# Supply_Sampler.net
KiCad netlist of a schematic drawn in Altium Designer
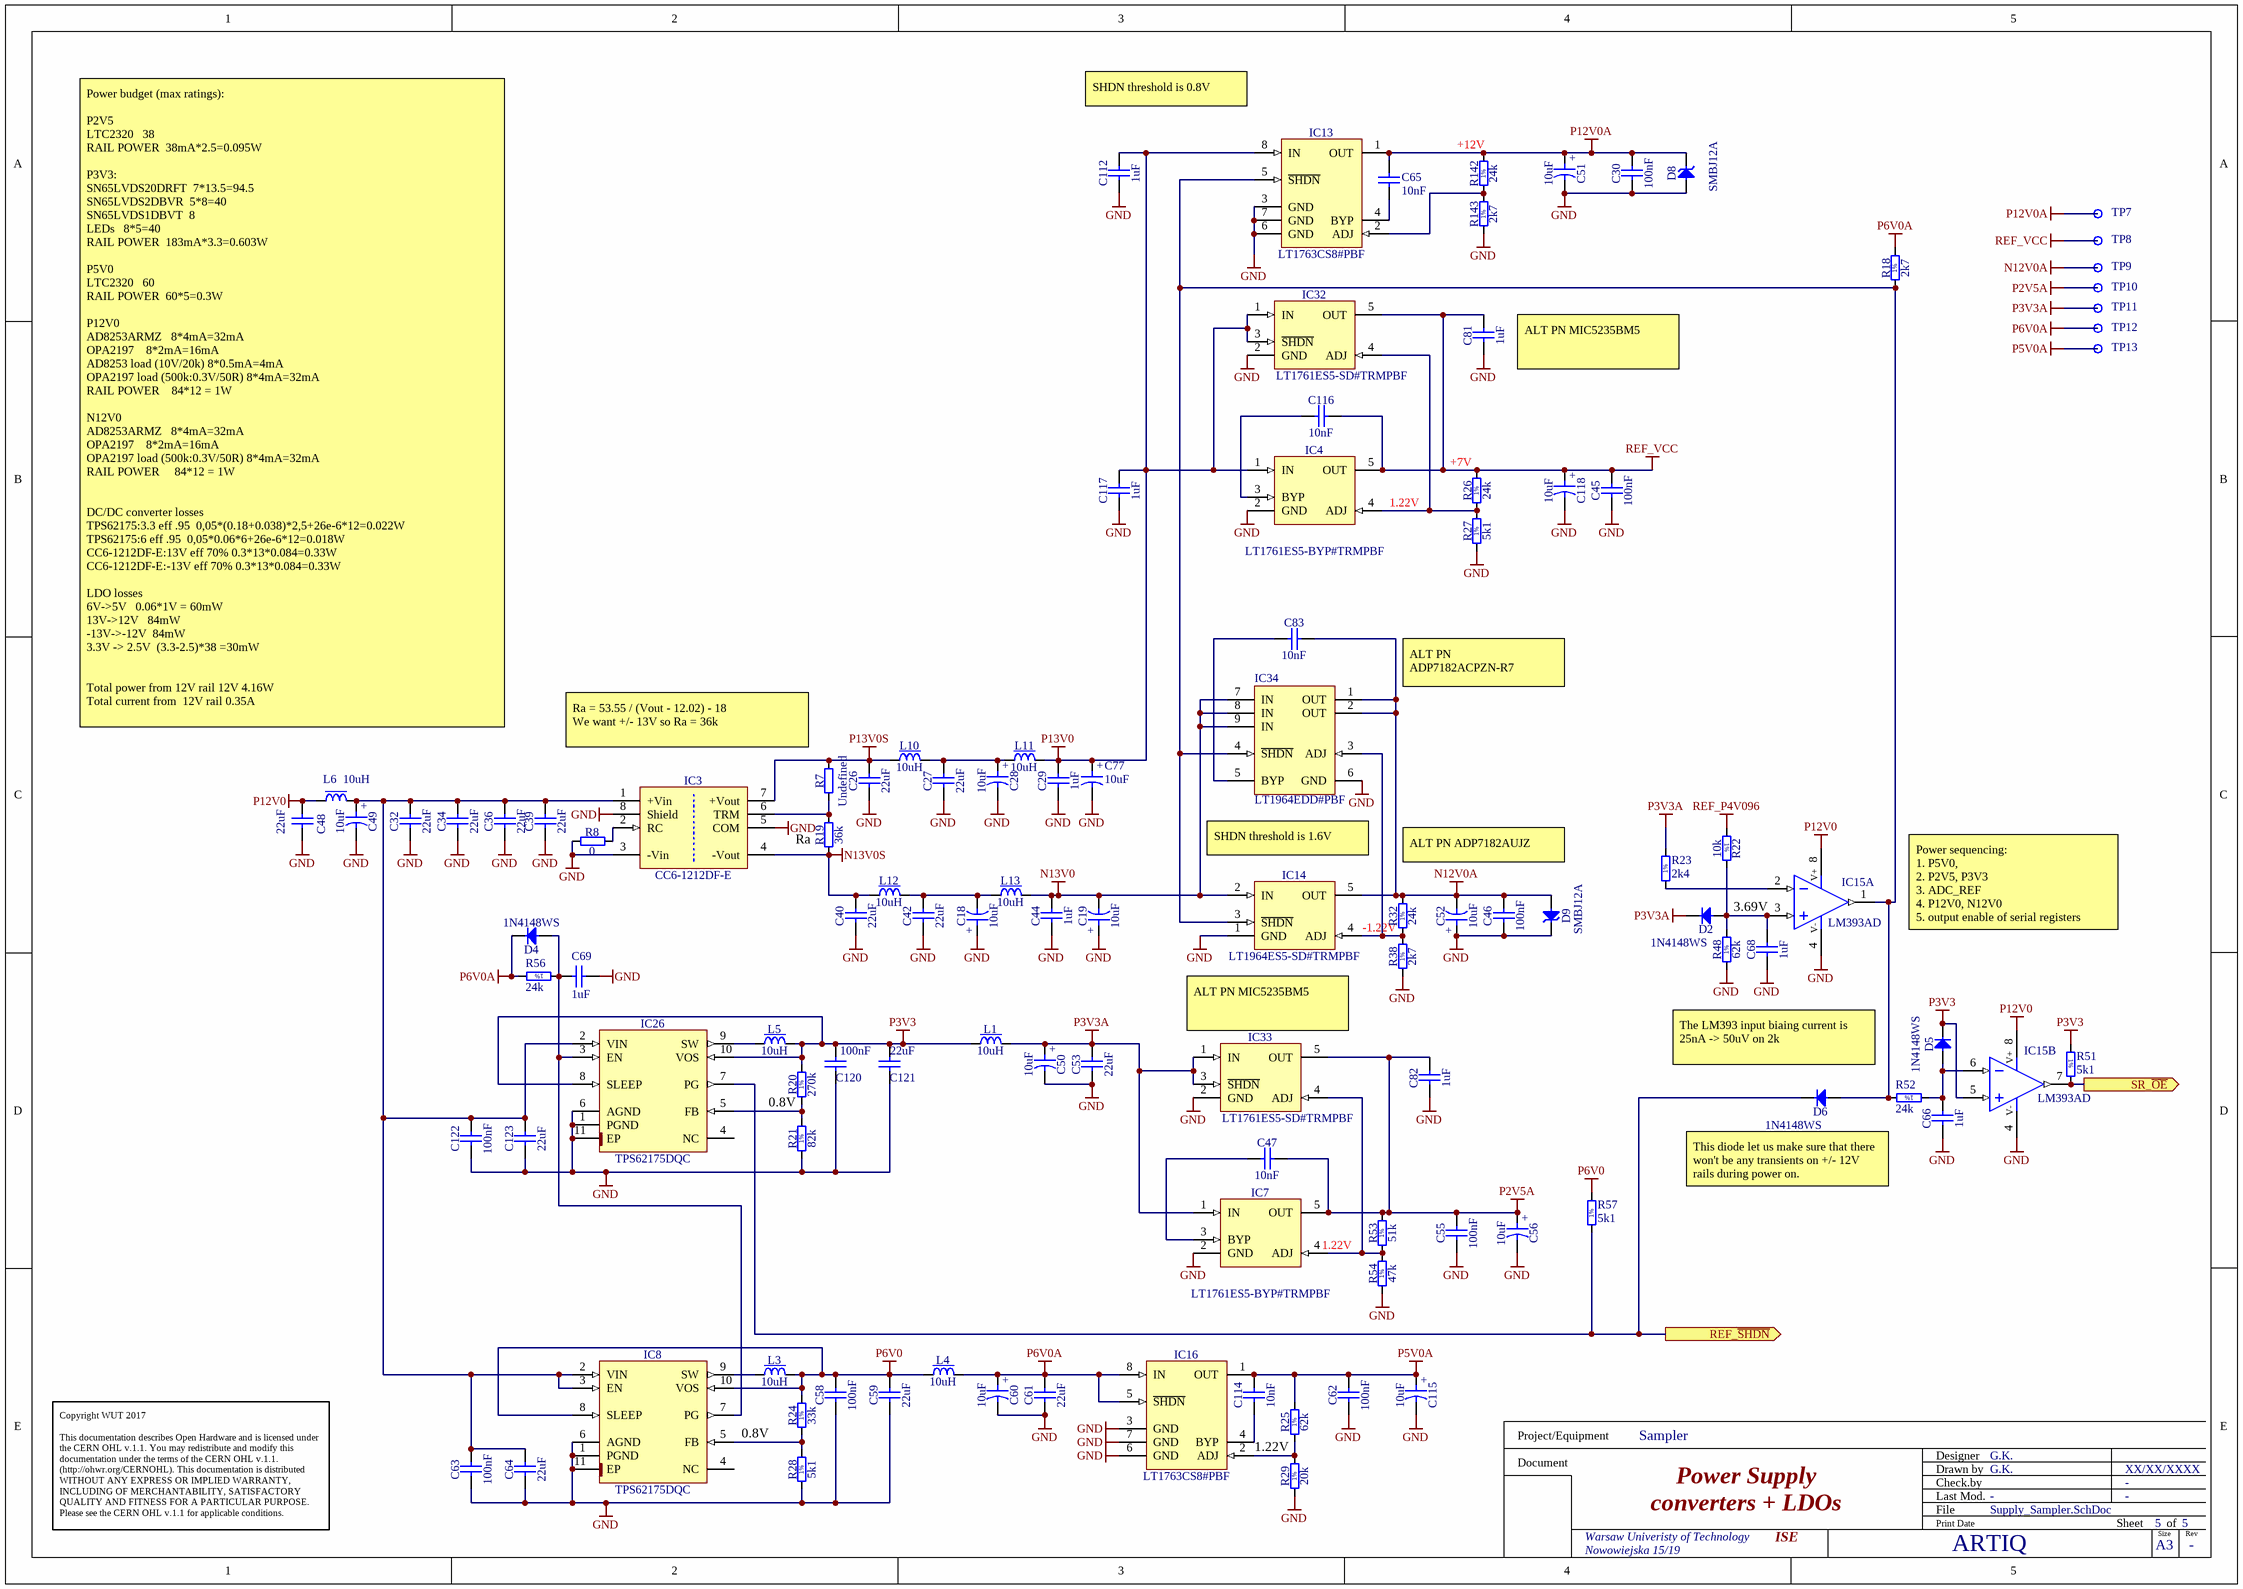
[diagram p0: Supply_Sampler.SchDoc]

(export (version "E")
  (design (tool "Eeschema 10.0.6"))
  (components
    (comp (ref "C18")
      (value "10uF")
      (footprint "CAPMP3216X180N")
      (description "Polarised capacitor")
      (fields (field (name "PART NUMBER") "CTE3216-18_10UF_16V_20%_AVX_TCJ") (field (name "VOLTAGE") "16V"))
      (libsource (lib "Capacitors") (part "Capacitor - polarized"))
    )
    (comp (ref "C19")
      (value "10uF")
      (footprint "CAPMP3216X180N")
      (description "Polarised capacitor")
      (fields (field (name "PART NUMBER") "CTE3216-18_10UF_16V_20%_AVX_TCJ") (field (name "VOLTAGE") "16V"))
      (libsource (lib "Capacitors") (part "Capacitor - polarized"))
    )
    (comp (ref "C26")
      (value "22uF")
      (footprint "CAPC2012X135N")
      (description "Non-polarised capacitor")
      (fields (field (name "PART NUMBER") "CC0805_22UF_16V_10%_X5R") (field (name "VOLTAGE") "16V"))
      (libsource (lib "Capacitors") (part "Capacitor - non polarized"))
    )
    (comp (ref "C27")
      (value "22uF")
      (footprint "CAPC2012X135N")
      (description "Non-polarised capacitor")
      (fields (field (name "PART NUMBER") "CC0805_22UF_16V_10%_X5R") (field (name "VOLTAGE") "16V"))
      (libsource (lib "Capacitors") (part "Capacitor - non polarized"))
    )
    (comp (ref "C28")
      (value "10uF")
      (footprint "CAPMP3216X180N")
      (description "Polarised capacitor")
      (fields (field (name "PART NUMBER") "CTE3216-18_10UF_16V_20%_AVX_TCJ") (field (name "VOLTAGE") "16V"))
      (libsource (lib "Capacitors") (part "Capacitor - polarized"))
    )
    (comp (ref "C29")
      (value "1uF")
      (footprint "CAPC1608X87N")
      (description "Non-polarised capacitor")
      (fields (field (name "PART NUMBER") "CC0603_1UF_25V_10%_X7R") (field (name "VOLTAGE") "25V"))
      (libsource (lib "Capacitors") (part "Capacitor - non polarized"))
    )
    (comp (ref "C30")
      (value "100nF")
      (footprint "CAPC1005X55N")
      (description "Non-polarised capacitor")
      (fields (field (name "PART NUMBER") "CC0402_100NF_16V_10%_X5R") (field (name "VOLTAGE") "16V"))
      (libsource (lib "Capacitors") (part "Capacitor - non polarized"))
    )
    (comp (ref "C32")
      (value "22uF")
      (footprint "CAPC2012X135N")
      (description "Non-polarised capacitor")
      (fields (field (name "PART NUMBER") "CC0805_22UF_16V_10%_X5R") (field (name "VOLTAGE") "16V"))
      (libsource (lib "Capacitors") (part "Capacitor - non polarized"))
    )
    (comp (ref "C34")
      (value "22uF")
      (footprint "CAPC2012X135N")
      (description "Non-polarised capacitor")
      (fields (field (name "PART NUMBER") "CC0805_22UF_16V_10%_X5R") (field (name "VOLTAGE") "16V"))
      (libsource (lib "Capacitors") (part "Capacitor - non polarized"))
    )
    (comp (ref "C36")
      (value "22uF")
      (footprint "CAPC2012X135N")
      (description "Non-polarised capacitor")
      (fields (field (name "PART NUMBER") "CC0805_22UF_16V_10%_X5R") (field (name "VOLTAGE") "16V"))
      (libsource (lib "Capacitors") (part "Capacitor - non polarized"))
    )
    (comp (ref "C39")
      (value "22uF")
      (footprint "CAPC2012X135N")
      (description "Non-polarised capacitor")
      (fields (field (name "PART NUMBER") "CC0805_22UF_16V_10%_X5R") (field (name "VOLTAGE") "16V"))
      (libsource (lib "Capacitors") (part "Capacitor - non polarized"))
    )
    (comp (ref "C40")
      (value "22uF")
      (footprint "CAPC2012X135N")
      (description "Non-polarised capacitor")
      (fields (field (name "PART NUMBER") "CC0805_22UF_16V_10%_X5R") (field (name "VOLTAGE") "16V"))
      (libsource (lib "Capacitors") (part "Capacitor - non polarized"))
    )
    (comp (ref "C42")
      (value "22uF")
      (footprint "CAPC2012X135N")
      (description "Non-polarised capacitor")
      (fields (field (name "PART NUMBER") "CC0805_22UF_16V_10%_X5R") (field (name "VOLTAGE") "16V"))
      (libsource (lib "Capacitors") (part "Capacitor - non polarized"))
    )
    (comp (ref "C44")
      (value "1uF")
      (footprint "CAPC1608X87N")
      (description "Non-polarised capacitor")
      (fields (field (name "PART NUMBER") "CC0603_1UF_25V_10%_X7R") (field (name "VOLTAGE") "25V"))
      (libsource (lib "Capacitors") (part "Capacitor - non polarized"))
    )
    (comp (ref "C45")
      (value "100nF")
      (footprint "CAPC1005X55N")
      (description "Non-polarised capacitor")
      (fields (field (name "PART NUMBER") "CC0402_100NF_16V_10%_X5R") (field (name "VOLTAGE") "16V"))
      (libsource (lib "Capacitors") (part "Capacitor - non polarized"))
    )
    (comp (ref "C46")
      (value "100nF")
      (footprint "CAPC1005X55N")
      (description "Non-polarised capacitor")
      (fields (field (name "PART NUMBER") "CC0402_100NF_16V_10%_X5R") (field (name "VOLTAGE") "16V"))
      (libsource (lib "Capacitors") (part "Capacitor - non polarized"))
    )
    (comp (ref "C47")
      (value "10nF")
      (footprint "CAPC1608X87N")
      (description "Non-polarised capacitor")
      (fields (field (name "PART NUMBER") "CC0603_10NF_50V_10%_X7R") (field (name "VOLTAGE") "50V"))
      (libsource (lib "Capacitors") (part "Capacitor - non polarized"))
    )
    (comp (ref "C48")
      (value "22uF")
      (footprint "CAPC2012X135N")
      (description "Non-polarised capacitor")
      (fields (field (name "PART NUMBER") "CC0805_22UF_16V_10%_X5R") (field (name "VOLTAGE") "16V"))
      (libsource (lib "Capacitors") (part "Capacitor - non polarized"))
    )
    (comp (ref "C49")
      (value "10uF")
      (footprint "CAPMP3216X180N")
      (description "Polarised capacitor")
      (fields (field (name "PART NUMBER") "CTE3216-18_10UF_16V_20%_AVX_TCJ") (field (name "VOLTAGE") "16V"))
      (libsource (lib "Capacitors") (part "Capacitor - polarized"))
    )
    (comp (ref "C50")
      (value "10uF")
      (footprint "CAPMP3216X180N")
      (description "Polarised capacitor")
      (fields (field (name "PART NUMBER") "CTE3216-18_10UF_16V_20%_AVX_TCJ") (field (name "VOLTAGE") "16V"))
      (libsource (lib "Capacitors") (part "Capacitor - polarized"))
    )
    (comp (ref "C51")
      (value "10uF")
      (footprint "CAPMP3216X180N")
      (description "Polarised capacitor")
      (fields (field (name "PART NUMBER") "CTE3216-18_10UF_16V_20%_AVX_TCJ") (field (name "VOLTAGE") "16V"))
      (libsource (lib "Capacitors") (part "Capacitor - polarized"))
    )
    (comp (ref "C52")
      (value "10uF")
      (footprint "CAPMP3216X180N")
      (description "Polarised capacitor")
      (fields (field (name "PART NUMBER") "CTE3216-18_10UF_16V_20%_AVX_TCJ") (field (name "VOLTAGE") "16V"))
      (libsource (lib "Capacitors") (part "Capacitor - polarized"))
    )
    (comp (ref "C53")
      (value "22uF")
      (footprint "CAPC2012X135N")
      (description "Non-polarised capacitor")
      (fields (field (name "PART NUMBER") "CC0805_22UF_16V_10%_X5R") (field (name "VOLTAGE") "16V"))
      (libsource (lib "Capacitors") (part "Capacitor - non polarized"))
    )
    (comp (ref "C55")
      (value "100nF")
      (footprint "CAPC1005X55N")
      (description "Non-polarised capacitor")
      (fields (field (name "PART NUMBER") "CC0402_100NF_16V_10%_X5R") (field (name "VOLTAGE") "16V"))
      (libsource (lib "Capacitors") (part "Capacitor - non polarized"))
    )
    (comp (ref "C56")
      (value "10uF")
      (footprint "CAPMP3216X180N")
      (description "Polarised capacitor")
      (fields (field (name "PART NUMBER") "CTE3216-18_10UF_16V_20%_AVX_TCJ") (field (name "VOLTAGE") "16V"))
      (libsource (lib "Capacitors") (part "Capacitor - polarized"))
    )
    (comp (ref "C58")
      (value "100nF")
      (footprint "CAPC1005X55N")
      (description "Non-polarised capacitor")
      (fields (field (name "PART NUMBER") "CC0402_100NF_16V_10%_X5R") (field (name "VOLTAGE") "16V"))
      (libsource (lib "Capacitors") (part "Capacitor - non polarized"))
    )
    (comp (ref "C59")
      (value "22uF")
      (footprint "CAPC2012X135N")
      (description "Non-polarised capacitor")
      (fields (field (name "PART NUMBER") "CC0805_22UF_16V_10%_X5R") (field (name "VOLTAGE") "16V"))
      (libsource (lib "Capacitors") (part "Capacitor - non polarized"))
    )
    (comp (ref "C60")
      (value "10uF")
      (footprint "CAPMP3216X180N")
      (description "Polarised capacitor")
      (fields (field (name "PART NUMBER") "CTE3216-18_10UF_16V_20%_AVX_TCJ") (field (name "VOLTAGE") "16V"))
      (libsource (lib "Capacitors") (part "Capacitor - polarized"))
    )
    (comp (ref "C61")
      (value "22uF")
      (footprint "CAPC2012X135N")
      (description "Non-polarised capacitor")
      (fields (field (name "PART NUMBER") "CC0805_22UF_16V_10%_X5R") (field (name "VOLTAGE") "16V"))
      (libsource (lib "Capacitors") (part "Capacitor - non polarized"))
    )
    (comp (ref "C62")
      (value "100nF")
      (footprint "CAPC1005X55N")
      (description "Non-polarised capacitor")
      (fields (field (name "PART NUMBER") "CC0402_100NF_16V_10%_X5R") (field (name "VOLTAGE") "16V"))
      (libsource (lib "Capacitors") (part "Capacitor - non polarized"))
    )
    (comp (ref "C63")
      (value "100nF")
      (footprint "CAPC1005X55N")
      (description "Non-polarised capacitor")
      (fields (field (name "PART NUMBER") "CC0402_100NF_16V_10%_X5R") (field (name "VOLTAGE") "16V"))
      (libsource (lib "Capacitors") (part "Capacitor - non polarized"))
    )
    (comp (ref "C64")
      (value "22uF")
      (footprint "CAPC2012X135N")
      (description "Non-polarised capacitor")
      (fields (field (name "PART NUMBER") "CC0805_22UF_16V_10%_X5R") (field (name "VOLTAGE") "16V"))
      (libsource (lib "Capacitors") (part "Capacitor - non polarized"))
    )
    (comp (ref "C65")
      (value "10nF")
      (footprint "CAPC1608X87N")
      (description "Non-polarised capacitor")
      (fields (field (name "PART NUMBER") "CC0603_10NF_50V_10%_X7R") (field (name "VOLTAGE") "50V"))
      (libsource (lib "Capacitors") (part "Capacitor - non polarized"))
    )
    (comp (ref "C66")
      (value "1uF")
      (footprint "CAPC1608X87N")
      (description "Non-polarised capacitor")
      (fields (field (name "PART NUMBER") "CC0603_1UF_25V_10%_X7R") (field (name "VOLTAGE") "25V"))
      (libsource (lib "Capacitors") (part "Capacitor - non polarized"))
    )
    (comp (ref "C68")
      (value "1uF")
      (footprint "CAPC1608X87N")
      (description "Non-polarised capacitor")
      (fields (field (name "PART NUMBER") "CC0603_1UF_25V_10%_X7R") (field (name "VOLTAGE") "25V"))
      (libsource (lib "Capacitors") (part "Capacitor - non polarized"))
    )
    (comp (ref "C69")
      (value "1uF")
      (footprint "CAPC1608X87N")
      (description "Non-polarised capacitor")
      (fields (field (name "PART NUMBER") "CC0603_1UF_25V_10%_X7R") (field (name "VOLTAGE") "25V"))
      (libsource (lib "Capacitors") (part "Capacitor - non polarized"))
    )
    (comp (ref "C77")
      (value "10uF")
      (footprint "CAPMP3216X180N")
      (description "Polarised capacitor")
      (fields (field (name "PART NUMBER") "CTE3216-18_10UF_16V_20%_AVX_TCJ") (field (name "VOLTAGE") "16V"))
      (libsource (lib "Capacitors") (part "Capacitor - polarized"))
    )
    (comp (ref "C81")
      (value "1uF")
      (footprint "CAPC1608X87N")
      (description "Non-polarised capacitor")
      (fields (field (name "PART NUMBER") "CC0603_1UF_25V_10%_X7R") (field (name "VOLTAGE") "25V"))
      (libsource (lib "Capacitors") (part "Capacitor - non polarized"))
    )
    (comp (ref "C82")
      (value "1uF")
      (footprint "CAPC1608X87N")
      (description "Non-polarised capacitor")
      (fields (field (name "PART NUMBER") "CC0603_1UF_25V_10%_X7R") (field (name "VOLTAGE") "25V"))
      (libsource (lib "Capacitors") (part "Capacitor - non polarized"))
    )
    (comp (ref "C83")
      (value "10nF")
      (footprint "CAPC1608X87N")
      (description "Non-polarised capacitor")
      (fields (field (name "PART NUMBER") "CC0603_10NF_50V_10%_X7R") (field (name "VOLTAGE") "50V"))
      (libsource (lib "Capacitors") (part "Capacitor - non polarized"))
    )
    (comp (ref "C112")
      (value "1uF")
      (footprint "CAPC1608X87N")
      (description "Non-polarised capacitor")
      (fields (field (name "PART NUMBER") "CC0603_1UF_25V_10%_X7R") (field (name "VOLTAGE") "25V"))
      (libsource (lib "Capacitors") (part "Capacitor - non polarized"))
    )
    (comp (ref "C114")
      (value "10nF")
      (footprint "CAPC1608X87N")
      (description "Non-polarised capacitor")
      (fields (field (name "PART NUMBER") "CC0603_10NF_50V_10%_X7R") (field (name "VOLTAGE") "50V"))
      (libsource (lib "Capacitors") (part "Capacitor - non polarized"))
    )
    (comp (ref "C115")
      (value "10uF")
      (footprint "CAPMP3216X180N")
      (description "Polarised capacitor")
      (fields (field (name "PART NUMBER") "CTE3216-18_10UF_16V_20%_AVX_TCJ") (field (name "VOLTAGE") "16V"))
      (libsource (lib "Capacitors") (part "Capacitor - polarized"))
    )
    (comp (ref "C116")
      (value "10nF")
      (footprint "CAPC1608X87N")
      (description "Non-polarised capacitor")
      (fields (field (name "PART NUMBER") "CC0603_10NF_50V_10%_X7R") (field (name "VOLTAGE") "50V"))
      (libsource (lib "Capacitors") (part "Capacitor - non polarized"))
    )
    (comp (ref "C117")
      (value "1uF")
      (footprint "CAPC1608X87N")
      (description "Non-polarised capacitor")
      (fields (field (name "PART NUMBER") "CC0603_1UF_25V_10%_X7R") (field (name "VOLTAGE") "25V"))
      (libsource (lib "Capacitors") (part "Capacitor - non polarized"))
    )
    (comp (ref "C118")
      (value "10uF")
      (footprint "CAPMP3216X180N")
      (description "Polarised capacitor")
      (fields (field (name "PART NUMBER") "CTE3216-18_10UF_16V_20%_AVX_TCJ") (field (name "VOLTAGE") "16V"))
      (libsource (lib "Capacitors") (part "Capacitor - polarized"))
    )
    (comp (ref "C120")
      (value "100nF")
      (footprint "CAPC1005X55N")
      (description "Non-polarised capacitor")
      (fields (field (name "PART NUMBER") "CC0402_100NF_16V_10%_X5R") (field (name "VOLTAGE") "16V"))
      (libsource (lib "Capacitors") (part "Capacitor - non polarized"))
    )
    (comp (ref "C121")
      (value "22uF")
      (footprint "CAPC2012X135N")
      (description "Non-polarised capacitor")
      (fields (field (name "PART NUMBER") "CC0805_22UF_16V_10%_X5R") (field (name "VOLTAGE") "16V"))
      (libsource (lib "Capacitors") (part "Capacitor - non polarized"))
    )
    (comp (ref "C122")
      (value "100nF")
      (footprint "CAPC1005X55N")
      (description "Non-polarised capacitor")
      (fields (field (name "PART NUMBER") "CC0402_100NF_16V_10%_X5R") (field (name "VOLTAGE") "16V"))
      (libsource (lib "Capacitors") (part "Capacitor - non polarized"))
    )
    (comp (ref "C123")
      (value "22uF")
      (footprint "CAPC2012X135N")
      (description "Non-polarised capacitor")
      (fields (field (name "PART NUMBER") "CC0805_22UF_16V_10%_X5R") (field (name "VOLTAGE") "16V"))
      (libsource (lib "Capacitors") (part "Capacitor - non polarized"))
    )
    (comp (ref "D2")
      (value "1N4148WS")
      (footprint "SODFL2512X100N")
      (description "Diode")
      (fields (field (name "VOLTAGE") "75V") (field (name "POWER") "150mA"))
      (libsource (lib "ICs And Semiconductors") (part "Diode"))
    )
    (comp (ref "D4")
      (value "1N4148WS")
      (footprint "SODFL2512X100N")
      (description "Diode")
      (fields (field (name "VOLTAGE") "75V") (field (name "POWER") "150mA"))
      (libsource (lib "ICs And Semiconductors") (part "Diode"))
    )
    (comp (ref "D5")
      (value "1N4148WS")
      (footprint "SODFL2512X100N")
      (description "Diode")
      (fields (field (name "VOLTAGE") "75V") (field (name "POWER") "150mA"))
      (libsource (lib "ICs And Semiconductors") (part "Diode"))
    )
    (comp (ref "D6")
      (value "1N4148WS")
      (footprint "SODFL2512X100N")
      (description "Diode")
      (fields (field (name "VOLTAGE") "75V") (field (name "POWER") "150mA"))
      (libsource (lib "ICs And Semiconductors") (part "Diode"))
    )
    (comp (ref "D8")
      (value "SMBJ12A")
      (footprint "DIOM5336X265N")
      (description "Zener Diode")
      (fields (field (name "VOLTAGE") "12V") (field (name "POWER") "600W"))
      (libsource (lib "ICs And Semiconductors") (part "Diode Zener"))
    )
    (comp (ref "D9")
      (value "SMBJ12A")
      (footprint "DIOM5336X265N")
      (description "Zener Diode")
      (fields (field (name "VOLTAGE") "12V") (field (name "POWER") "600W"))
      (libsource (lib "ICs And Semiconductors") (part "Diode Zener"))
    )
    (comp (ref "IC3")
      (value "CC6-1212DF-E")
      (footprint "CC6-1212DF-E")
      (description "CONV DC/DC 6W DUAL 12V +-12V PCB")
      (fields (field (name "MANUFACTURER") "TDK-Lambda Americas Inc."))
      (libsource (lib "Regulators_SMPS") (part "DC/DC_CC6-1212DF-E"))
    )
    (comp (ref "IC4")
      (value "LT1761ES5-BYP#TRMPBF")
      (footprint "SOT95P280X100-5N")
      (description "100mA, Low Noise, LDO Micropower Adjustable Regulator in SOT-23")
      (fields (field (name "MANUFACTURER") "LINEAR TECHNOLOGY"))
      (libsource (lib "ICs And Semiconductors") (part "LT1761-BYP"))
    )
    (comp (ref "IC7")
      (value "LT1761ES5-BYP#TRMPBF")
      (footprint "SOT95P280X100-5N")
      (description "100mA, Low Noise, LDO Micropower Adjustable Regulator in SOT-23")
      (fields (field (name "MANUFACTURER") "LINEAR TECHNOLOGY"))
      (libsource (lib "ICs And Semiconductors") (part "LT1761-BYP"))
    )
    (comp (ref "IC8")
      (value "TPS62175DQC")
      (footprint "SON50P200X300X80-11N-R94X250")
      (description "4.75-28VDC to 1-6VDC, 500mA Step-Down Converter With Sleep Mode")
      (fields (field (name "MANUFACTURER") "TEXAS INSTRUMENTS"))
      (libsource (lib "ICs And Semiconductors") (part "TPS62175"))
    )
    (comp (ref "IC13")
      (value "LT1763CS8#PBF")
      (footprint "SOIC127P600X175-8N")
      (description "1.22V to 20V 500mA, Low Noise, LDO Adjustable Micropower Regulator")
      (fields (field (name "MANUFACTURER") "LINEAR TECHNOLOGY"))
      (libsource (lib "ICs And Semiconductors") (part "LT1763xS8"))
    )
    (comp (ref "IC14")
      (value "LT1964ES5-SD#TRMPBF")
      (footprint "SOT95P280X100-5N")
      (description "200mA, Low Noise, Low Dropout Negative Micropower Regulator")
      (fields (field (name "MANUFACTURER") "LINEAR TECHNOLOGY"))
      (libsource (lib "ICs And Semiconductors") (part "LT1964-SD"))
    )
    (comp (ref "IC15")
      (value "LM393AD")
      (footprint "SOIC127P600X175-8N")
      (description "Dual Operational Amplifier")
      (fields (field (name "MANUFACTURER") "TEXAS INSTRUMENTS"))
      (libsource (lib "ICs And Semiconductors") (part "Operational Amplifier x2 Type1"))
    )
    (comp (ref "IC16")
      (value "LT1763CS8#PBF")
      (footprint "SOIC127P600X175-8N")
      (description "1.22V to 20V 500mA, Low Noise, LDO Adjustable Micropower Regulator")
      (fields (field (name "MANUFACTURER") "LINEAR TECHNOLOGY"))
      (libsource (lib "ICs And Semiconductors") (part "LT1763xS8"))
    )
    (comp (ref "IC26")
      (value "TPS62175DQC")
      (footprint "SON50P200X300X80-11N-R94X250")
      (description "4.75-28VDC to 1-6VDC, 500mA Step-Down Converter With Sleep Mode")
      (fields (field (name "MANUFACTURER") "TEXAS INSTRUMENTS"))
      (libsource (lib "ICs And Semiconductors") (part "TPS62175"))
    )
    (comp (ref "IC32")
      (value "LT1761ES5-SD#TRMPBF")
      (footprint "SOT95P280X100-5N")
      (description "100mA, Low Noise, LDO Micropower Adjustable Regulator in SOT-23")
      (fields (field (name "MANUFACTURER") "LINEAR TECHNOLOGY"))
      (libsource (lib "ICs And Semiconductors") (part "LT1761-SD"))
    )
    (comp (ref "IC33")
      (value "LT1761ES5-SD#TRMPBF")
      (footprint "SOT95P280X100-5N")
      (description "100mA, Low Noise, LDO Micropower Adjustable Regulator in SOT-23")
      (fields (field (name "MANUFACTURER") "LINEAR TECHNOLOGY"))
      (libsource (lib "ICs And Semiconductors") (part "LT1761-SD"))
    )
    (comp (ref "IC34")
      (value "LT1964EDD#PBF")
      (footprint "LT-DD-8_V")
      (fields (field (name "MANUFACTURER") "Linear Technology"))
      (libsource (lib "Altium Content Vault") (part "LT-LT1964-DD-8"))
    )
    (comp (ref "L1")
      (value "10uH")
      (footprint "IND_MURATA-PS_8400")
      (description "Inductor With Core")
      (fields (field (name "PART NUMBER") "IND_10UH_10%_MURATA-PS_8400") (field (name "POWER") "950mA"))
      (libsource (lib "Inductors & Transformers") (part "Inductor With Magnetic core"))
    )
    (comp (ref "L3")
      (value "10uH")
      (footprint "IND_MURATA-PS_8400")
      (description "Inductor With Core")
      (fields (field (name "PART NUMBER") "IND_10UH_10%_MURATA-PS_8400") (field (name "POWER") "950mA"))
      (libsource (lib "Inductors & Transformers") (part "Inductor With Magnetic core"))
    )
    (comp (ref "L4")
      (value "10uH")
      (footprint "IND_MURATA-PS_8400")
      (description "Inductor With Core")
      (fields (field (name "PART NUMBER") "IND_10UH_10%_MURATA-PS_8400") (field (name "POWER") "950mA"))
      (libsource (lib "Inductors & Transformers") (part "Inductor With Magnetic core"))
    )
    (comp (ref "L5")
      (value "10uH")
      (footprint "IND_MURATA-PS_8400")
      (description "Inductor With Core")
      (fields (field (name "PART NUMBER") "IND_10UH_10%_MURATA-PS_8400") (field (name "POWER") "950mA"))
      (libsource (lib "Inductors & Transformers") (part "Inductor With Magnetic core"))
    )
    (comp (ref "L6")
      (value "10uH")
      (footprint "IND_MURATA-PS_8400")
      (description "Inductor With Core")
      (fields (field (name "PART NUMBER") "IND_10UH_10%_MURATA-PS_8400") (field (name "POWER") "950mA"))
      (libsource (lib "Inductors & Transformers") (part "Inductor With Magnetic core"))
    )
    (comp (ref "L10")
      (value "10uH")
      (footprint "IND_MURATA-PS_8400")
      (description "Inductor With Core")
      (fields (field (name "PART NUMBER") "IND_10UH_10%_MURATA-PS_8400") (field (name "POWER") "950mA"))
      (libsource (lib "Inductors & Transformers") (part "Inductor With Magnetic core"))
    )
    (comp (ref "L11")
      (value "10uH")
      (footprint "IND_MURATA-PS_8400")
      (description "Inductor With Core")
      (fields (field (name "PART NUMBER") "IND_10UH_10%_MURATA-PS_8400") (field (name "POWER") "950mA"))
      (libsource (lib "Inductors & Transformers") (part "Inductor With Magnetic core"))
    )
    (comp (ref "L12")
      (value "10uH")
      (footprint "IND_MURATA-PS_8400")
      (description "Inductor With Core")
      (fields (field (name "PART NUMBER") "IND_10UH_10%_MURATA-PS_8400") (field (name "POWER") "950mA"))
      (libsource (lib "Inductors & Transformers") (part "Inductor With Magnetic core"))
    )
    (comp (ref "L13")
      (value "10uH")
      (footprint "IND_MURATA-PS_8400")
      (description "Inductor With Core")
      (fields (field (name "PART NUMBER") "IND_10UH_10%_MURATA-PS_8400") (field (name "POWER") "950mA"))
      (libsource (lib "Inductors & Transformers") (part "Inductor With Magnetic core"))
    )
    (comp (ref "R7")
      (value "Undefined")
      (footprint "RESC1608X55N")
      (description "Resistor")
      (fields (field (name "PART NUMBER") "R0603_NO-VALUE"))
      (libsource (lib "Resistors") (part "Resistor"))
    )
    (comp (ref "R8")
      (value "0")
      (footprint "RESC1005X40N")
      (description "Resistor")
      (fields (field (name "PART NUMBER") "R0402_0R_JUMPER") (field (name "MANUFACTURER") "GENERIC"))
      (libsource (lib "Resistors") (part "Resistor"))
    )
    (comp (ref "R18")
      (value "2k7")
      (footprint "RESC1608X55N")
      (description "Resistor - 1%")
      (fields (field (name "PART NUMBER") "R0603_2K7_1%_0.1W_100PPM") (field (name "POWER") "0.1W"))
      (libsource (lib "Resistors") (part "Resistor - 1%"))
    )
    (comp (ref "R19")
      (value "36k")
      (footprint "RESC1608X55N")
      (description "Resistor - 1%")
      (fields (field (name "PART NUMBER") "R0603_36K_1%_0.1W_100PPM") (field (name "POWER") "0.1W"))
      (libsource (lib "") (part "Resistor - 1%_1"))
    )
    (comp (ref "R20")
      (value "270k")
      (footprint "RESC1608X55N")
      (description "Resistor - 1%")
      (fields (field (name "PART NUMBER") "R0603_270K_1%_0.1W_100PPM") (field (name "POWER") "0.1W"))
      (libsource (lib "Resistors") (part "Resistor - 1%"))
    )
    (comp (ref "R21")
      (value "82k")
      (footprint "RESC1608X55N")
      (description "Resistor - 1%")
      (fields (field (name "PART NUMBER") "R0603_82K_1%_0.1W_100PPM") (field (name "POWER") "0.1W"))
      (libsource (lib "Resistors") (part "Resistor - 1%"))
    )
    (comp (ref "R22")
      (value "10k")
      (footprint "RESC1005X40N")
      (description "Resistor - 1%")
      (fields (field (name "PART NUMBER") "R0402_10K_1%_0.0625W_100PPM") (field (name "POWER") "0.0625W"))
      (libsource (lib "Resistors") (part "Resistor - 1%"))
    )
    (comp (ref "R23")
      (value "2k4")
      (footprint "RESC1005X40N")
      (description "Resistor - 1%")
      (fields (field (name "PART NUMBER") "R0402_2K4_1%_0.0625W_100PPM") (field (name "POWER") "0.0625W"))
      (libsource (lib "Resistors") (part "Resistor - 1%"))
    )
    (comp (ref "R24")
      (value "33k")
      (footprint "RESC1005X40N")
      (description "Resistor - 1%")
      (fields (field (name "PART NUMBER") "R0402_33K_1%_0.0625W_100PPM") (field (name "POWER") "0.0625W"))
      (libsource (lib "Resistors") (part "Resistor - 1%"))
    )
    (comp (ref "R25")
      (value "62k")
      (footprint "RESC1005X40N")
      (description "Resistor - 1%")
      (fields (field (name "PART NUMBER") "R0402_62K_1%_0.0625W_100PPM") (field (name "POWER") "0.0625W"))
      (libsource (lib "Resistors") (part "Resistor - 1%"))
    )
    (comp (ref "R26")
      (value "24k")
      (footprint "RESC1608X55N")
      (description "Resistor - 1%")
      (fields (field (name "PART NUMBER") "R0603_24K_1%_0.1W_100PPM") (field (name "POWER") "0.1W"))
      (libsource (lib "Resistors") (part "Resistor - 1%"))
    )
    (comp (ref "R27")
      (value "5k1")
      (footprint "RESC1005X40N")
      (description "Resistor - 1%")
      (fields (field (name "PART NUMBER") "R0402_5K1_1%_0.0625W_100PPM") (field (name "POWER") "0.0625W"))
      (libsource (lib "Resistors") (part "Resistor - 1%"))
    )
    (comp (ref "R28")
      (value "5k1")
      (footprint "RESC1005X40N")
      (description "Resistor - 1%")
      (fields (field (name "PART NUMBER") "R0402_5K1_1%_0.0625W_100PPM") (field (name "POWER") "0.0625W"))
      (libsource (lib "Resistors") (part "Resistor - 1%"))
    )
    (comp (ref "R29")
      (value "20k")
      (footprint "RESC1005X40N")
      (description "Resistor - 1%")
      (fields (field (name "PART NUMBER") "R0402_20K_1%_0.0625W_100PPM") (field (name "POWER") "0.0625W"))
      (libsource (lib "Resistors") (part "Resistor - 1%"))
    )
    (comp (ref "R32")
      (value "24k")
      (footprint "RESC1608X55N")
      (description "Resistor - 1%")
      (fields (field (name "PART NUMBER") "R0603_24K_1%_0.1W_100PPM") (field (name "POWER") "0.1W"))
      (libsource (lib "Resistors") (part "Resistor - 1%"))
    )
    (comp (ref "R38")
      (value "2k7")
      (footprint "RESC1608X55N")
      (description "Resistor - 1%")
      (fields (field (name "PART NUMBER") "R0603_2K7_1%_0.1W_100PPM") (field (name "POWER") "0.1W"))
      (libsource (lib "Resistors") (part "Resistor - 1%"))
    )
    (comp (ref "R48")
      (value "62k")
      (footprint "RESC1005X40N")
      (description "Resistor - 1%")
      (fields (field (name "PART NUMBER") "R0402_62K_1%_0.0625W_100PPM") (field (name "POWER") "0.0625W"))
      (libsource (lib "Resistors") (part "Resistor - 1%"))
    )
    (comp (ref "R51")
      (value "5k1")
      (footprint "RESC1005X40N")
      (description "Resistor - 1%")
      (fields (field (name "PART NUMBER") "R0402_5K1_1%_0.0625W_100PPM") (field (name "POWER") "0.0625W"))
      (libsource (lib "Resistors") (part "Resistor - 1%"))
    )
    (comp (ref "R52")
      (value "24k")
      (footprint "RESC1608X55N")
      (description "Resistor - 1%")
      (fields (field (name "PART NUMBER") "R0603_24K_1%_0.1W_100PPM") (field (name "POWER") "0.1W"))
      (libsource (lib "Resistors") (part "Resistor - 1%"))
    )
    (comp (ref "R53")
      (value "51k")
      (footprint "RESC1005X40N")
      (description "Resistor - 1%")
      (fields (field (name "PART NUMBER") "R0402_51K_1%_0.0625W_100PPM") (field (name "POWER") "0.0625W"))
      (libsource (lib "Resistors") (part "Resistor - 1%"))
    )
    (comp (ref "R54")
      (value "47k")
      (footprint "RESC1005X40N")
      (description "Resistor - 1%")
      (fields (field (name "PART NUMBER") "R0402_47K_1%_0.0625W_100PPM") (field (name "POWER") "0.0625W"))
      (libsource (lib "Resistors") (part "Resistor - 1%"))
    )
    (comp (ref "R56")
      (value "24k")
      (footprint "RESC1608X55N")
      (description "Resistor - 1%")
      (fields (field (name "PART NUMBER") "R0603_24K_1%_0.1W_100PPM") (field (name "POWER") "0.1W"))
      (libsource (lib "Resistors") (part "Resistor - 1%"))
    )
    (comp (ref "R57")
      (value "5k1")
      (footprint "RESC1005X40N")
      (description "Resistor - 1%")
      (fields (field (name "PART NUMBER") "R0402_5K1_1%_0.0625W_100PPM") (field (name "POWER") "0.0625W"))
      (libsource (lib "Resistors") (part "Resistor - 1%"))
    )
    (comp (ref "R142")
      (value "24k")
      (footprint "RESC1608X55N")
      (description "Resistor - 1%")
      (fields (field (name "PART NUMBER") "R0603_24K_1%_0.1W_100PPM") (field (name "POWER") "0.1W"))
      (libsource (lib "Resistors") (part "Resistor - 1%"))
    )
    (comp (ref "R143")
      (value "2k7")
      (footprint "RESC1608X55N")
      (description "Resistor - 1%")
      (fields (field (name "PART NUMBER") "R0603_2K7_1%_0.1W_100PPM") (field (name "POWER") "0.1W"))
      (libsource (lib "Resistors") (part "Resistor - 1%"))
    )
    (comp (ref "TP7")
      (value "Test Point")
      (footprint "TPS127")
      (fields (field (name "PART NUMBER") "SMD_PAD_1.27X1.27MM"))
      (libsource (lib "Eletro-mechanical") (part "Test Point"))
    )
    (comp (ref "TP8")
      (value "Test Point")
      (footprint "TPS127")
      (fields (field (name "PART NUMBER") "SMD_PAD_1.27X1.27MM"))
      (libsource (lib "Eletro-mechanical") (part "Test Point"))
    )
    (comp (ref "TP9")
      (value "Test Point")
      (footprint "TPS127")
      (fields (field (name "PART NUMBER") "SMD_PAD_1.27X1.27MM"))
      (libsource (lib "Eletro-mechanical") (part "Test Point"))
    )
    (comp (ref "TP10")
      (value "Test Point")
      (footprint "TPS127")
      (fields (field (name "PART NUMBER") "SMD_PAD_1.27X1.27MM"))
      (libsource (lib "Eletro-mechanical") (part "Test Point"))
    )
    (comp (ref "TP11")
      (value "Test Point")
      (footprint "TPS127")
      (fields (field (name "PART NUMBER") "SMD_PAD_1.27X1.27MM"))
      (libsource (lib "Eletro-mechanical") (part "Test Point"))
    )
    (comp (ref "TP12")
      (value "Test Point")
      (footprint "TPS127")
      (fields (field (name "PART NUMBER") "SMD_PAD_1.27X1.27MM"))
      (libsource (lib "Eletro-mechanical") (part "Test Point"))
    )
    (comp (ref "TP13")
      (value "Test Point")
      (footprint "TPS127")
      (fields (field (name "PART NUMBER") "SMD_PAD_1.27X1.27MM"))
      (libsource (lib "Eletro-mechanical") (part "Test Point"))
    )
  )
  (nets
    (net (code "1") (name "/REF_~{SHDN}") (class "Default")
      (node (ref "D6") (pin "1") (pinfunction "C_1") (pintype "passive"))
      (node (ref "IC26") (pin "7") (pinfunction "PG_7") (pintype "output"))
      (node (ref "R57") (pin "1") (pinfunction "1_1") (pintype "passive"))
    )
    (net (code "2") (name "/SR_~{OE}") (class "Default")
      (node (ref "IC15") (pin "7") (pinfunction "OUT_7") (pintype "output"))
      (node (ref "R51") (pin "2") (pinfunction "2_2") (pintype "passive"))
    )
    (net (code "3") (name "GND") (class "Default")
      (node (ref "C112") (pin "1") (pinfunction "1_1") (pintype "passive"))
      (node (ref "C115") (pin "2") (pinfunction "2_2") (pintype "passive"))
      (node (ref "C117") (pin "1") (pinfunction "1_1") (pintype "passive"))
      (node (ref "C118") (pin "2") (pinfunction "2_2") (pintype "passive"))
      (node (ref "C120") (pin "1") (pinfunction "1_1") (pintype "passive"))
      (node (ref "C121") (pin "1") (pinfunction "1_1") (pintype "passive"))
      (node (ref "C122") (pin "1") (pinfunction "1_1") (pintype "passive"))
      (node (ref "C123") (pin "1") (pinfunction "1_1") (pintype "passive"))
      (node (ref "C18") (pin "1") (pinfunction "1_1") (pintype "passive"))
      (node (ref "C19") (pin "1") (pinfunction "1_1") (pintype "passive"))
      (node (ref "C26") (pin "1") (pinfunction "1_1") (pintype "passive"))
      (node (ref "C27") (pin "1") (pinfunction "1_1") (pintype "passive"))
      (node (ref "C28") (pin "2") (pinfunction "2_2") (pintype "passive"))
      (node (ref "C29") (pin "1") (pinfunction "1_1") (pintype "passive"))
      (node (ref "C30") (pin "1") (pinfunction "1_1") (pintype "passive"))
      (node (ref "C32") (pin "1") (pinfunction "1_1") (pintype "passive"))
      (node (ref "C34") (pin "1") (pinfunction "1_1") (pintype "passive"))
      (node (ref "C36") (pin "1") (pinfunction "1_1") (pintype "passive"))
      (node (ref "C39") (pin "1") (pinfunction "1_1") (pintype "passive"))
      (node (ref "C40") (pin "1") (pinfunction "1_1") (pintype "passive"))
      (node (ref "C42") (pin "1") (pinfunction "1_1") (pintype "passive"))
      (node (ref "C44") (pin "1") (pinfunction "1_1") (pintype "passive"))
      (node (ref "C45") (pin "1") (pinfunction "1_1") (pintype "passive"))
      (node (ref "C46") (pin "1") (pinfunction "1_1") (pintype "passive"))
      (node (ref "C48") (pin "1") (pinfunction "1_1") (pintype "passive"))
      (node (ref "C49") (pin "2") (pinfunction "2_2") (pintype "passive"))
      (node (ref "C50") (pin "2") (pinfunction "2_2") (pintype "passive"))
      (node (ref "C51") (pin "2") (pinfunction "2_2") (pintype "passive"))
      (node (ref "C52") (pin "1") (pinfunction "1_1") (pintype "passive"))
      (node (ref "C53") (pin "1") (pinfunction "1_1") (pintype "passive"))
      (node (ref "C55") (pin "1") (pinfunction "1_1") (pintype "passive"))
      (node (ref "C56") (pin "2") (pinfunction "2_2") (pintype "passive"))
      (node (ref "C58") (pin "1") (pinfunction "1_1") (pintype "passive"))
      (node (ref "C59") (pin "1") (pinfunction "1_1") (pintype "passive"))
      (node (ref "C60") (pin "2") (pinfunction "2_2") (pintype "passive"))
      (node (ref "C61") (pin "1") (pinfunction "1_1") (pintype "passive"))
      (node (ref "C62") (pin "1") (pinfunction "1_1") (pintype "passive"))
      (node (ref "C63") (pin "1") (pinfunction "1_1") (pintype "passive"))
      (node (ref "C64") (pin "1") (pinfunction "1_1") (pintype "passive"))
      (node (ref "C66") (pin "1") (pinfunction "1_1") (pintype "passive"))
      (node (ref "C68") (pin "1") (pinfunction "1_1") (pintype "passive"))
      (node (ref "C69") (pin "1") (pinfunction "1_1") (pintype "passive"))
      (node (ref "C77") (pin "2") (pinfunction "2_2") (pintype "passive"))
      (node (ref "C81") (pin "1") (pinfunction "1_1") (pintype "passive"))
      (node (ref "C82") (pin "1") (pinfunction "1_1") (pintype "passive"))
      (node (ref "D8") (pin "2") (pinfunction "A_2") (pintype "passive"))
      (node (ref "D9") (pin "1") (pinfunction "C_1") (pintype "passive"))
      (node (ref "IC13") (pin "3") (pinfunction "GND_3") (pintype "power_in"))
      (node (ref "IC13") (pin "6") (pinfunction "GND_6") (pintype "power_in"))
      (node (ref "IC13") (pin "7") (pinfunction "GND_7") (pintype "power_in"))
      (node (ref "IC14") (pin "1") (pinfunction "GND_1") (pintype "power_in"))
      (node (ref "IC15") (pin "4") (pinfunction "V-_4") (pintype "power_in"))
      (node (ref "IC16") (pin "3") (pinfunction "GND_3") (pintype "power_in"))
      (node (ref "IC16") (pin "6") (pinfunction "GND_6") (pintype "power_in"))
      (node (ref "IC16") (pin "7") (pinfunction "GND_7") (pintype "power_in"))
      (node (ref "IC26") (pin "1") (pinfunction "PGND_1") (pintype "power_in"))
      (node (ref "IC26") (pin "11") (pinfunction "EP_11") (pintype "power_in"))
      (node (ref "IC26") (pin "6") (pinfunction "AGND_6") (pintype "power_in"))
      (node (ref "IC3") (pin "3") (pinfunction "-Vin_3") (pintype "power_in"))
      (node (ref "IC3") (pin "5") (pinfunction "COM_5") (pintype "power_in"))
      (node (ref "IC3") (pin "8") (pinfunction "Shield_8") (pintype "power_in"))
      (node (ref "IC32") (pin "2") (pinfunction "GND_2") (pintype "power_in"))
      (node (ref "IC33") (pin "2") (pinfunction "GND_2") (pintype "power_in"))
      (node (ref "IC34") (pin "6") (pinfunction "GND_6") (pintype "power_in"))
      (node (ref "IC4") (pin "2") (pinfunction "GND_2") (pintype "power_in"))
      (node (ref "IC7") (pin "2") (pinfunction "GND_2") (pintype "power_in"))
      (node (ref "IC8") (pin "1") (pinfunction "PGND_1") (pintype "power_in"))
      (node (ref "IC8") (pin "11") (pinfunction "EP_11") (pintype "power_in"))
      (node (ref "IC8") (pin "6") (pinfunction "AGND_6") (pintype "power_in"))
      (node (ref "R143") (pin "1") (pinfunction "1_1") (pintype "passive"))
      (node (ref "R21") (pin "1") (pinfunction "1_1") (pintype "passive"))
      (node (ref "R27") (pin "1") (pinfunction "1_1") (pintype "passive"))
      (node (ref "R28") (pin "1") (pinfunction "1_1") (pintype "passive"))
      (node (ref "R29") (pin "1") (pinfunction "1_1") (pintype "passive"))
      (node (ref "R38") (pin "1") (pinfunction "1_1") (pintype "passive"))
      (node (ref "R48") (pin "1") (pinfunction "1_1") (pintype "passive"))
      (node (ref "R54") (pin "1") (pinfunction "1_1") (pintype "passive"))
      (node (ref "R8") (pin "1") (pinfunction "1_1") (pintype "passive"))
    )
    (net (code "4") (name "N12V0A") (class "Default")
      (node (ref "C46") (pin "2") (pinfunction "2_2") (pintype "passive"))
      (node (ref "C52") (pin "2") (pinfunction "2_2") (pintype "passive"))
      (node (ref "C83") (pin "2") (pinfunction "2_2") (pintype "passive"))
      (node (ref "D9") (pin "2") (pinfunction "A_2") (pintype "passive"))
      (node (ref "IC14") (pin "5") (pinfunction "OUT_5") (pintype "power_in"))
      (node (ref "IC34") (pin "1") (pinfunction "OUT_1") (pintype "power_in"))
      (node (ref "IC34") (pin "2") (pinfunction "OUT_2") (pintype "power_in"))
      (node (ref "R32") (pin "2") (pinfunction "2_2") (pintype "passive"))
      (node (ref "TP9") (pin "1") (pinfunction "1_1") (pintype "bidirectional"))
    )
    (net (code "5") (name "N13V0") (class "Default")
      (node (ref "C19") (pin "2") (pinfunction "2_2") (pintype "passive"))
      (node (ref "C44") (pin "2") (pinfunction "2_2") (pintype "passive"))
      (node (ref "IC14") (pin "2") (pinfunction "IN_2") (pintype "input"))
      (node (ref "IC34") (pin "7") (pinfunction "IN_7") (pintype "power_in"))
      (node (ref "IC34") (pin "8") (pinfunction "IN_8") (pintype "power_in"))
      (node (ref "IC34") (pin "9") (pinfunction "IN_9") (pintype "power_in"))
      (node (ref "L13") (pin "2") (pinfunction "2_2") (pintype "passive"))
    )
    (net (code "6") (name "N13V0S") (class "Default")
      (node (ref "C40") (pin "2") (pinfunction "2_2") (pintype "passive"))
      (node (ref "IC3") (pin "4") (pinfunction "-Vout_4") (pintype "power_in"))
      (node (ref "L12") (pin "1") (pinfunction "1_1") (pintype "passive"))
      (node (ref "R19") (pin "1") (pinfunction "1_1") (pintype "passive"))
    )
    (net (code "7") (name "Net-(C18-Pad2)") (class "Default")
      (node (ref "C18") (pin "2") (pinfunction "2_2") (pintype "passive"))
      (node (ref "C42") (pin "2") (pinfunction "2_2") (pintype "passive"))
      (node (ref "L12") (pin "2") (pinfunction "2_2") (pintype "passive"))
      (node (ref "L13") (pin "1") (pinfunction "1_1") (pintype "passive"))
    )
    (net (code "8") (name "Net-(C27-Pad2)") (class "Default")
      (node (ref "C27") (pin "2") (pinfunction "2_2") (pintype "passive"))
      (node (ref "C28") (pin "1") (pinfunction "1_1") (pintype "passive"))
      (node (ref "L10") (pin "2") (pinfunction "2_2") (pintype "passive"))
      (node (ref "L11") (pin "1") (pinfunction "1_1") (pintype "passive"))
    )
    (net (code "9") (name "Net-(D2-A)") (class "Default")
      (node (ref "C68") (pin "2") (pinfunction "2_2") (pintype "passive"))
      (node (ref "D2") (pin "2") (pinfunction "A_2") (pintype "passive"))
      (node (ref "IC15") (pin "3") (pinfunction "IN+_3") (pintype "input"))
      (node (ref "R22") (pin "2") (pinfunction "2_2") (pintype "passive"))
      (node (ref "R48") (pin "2") (pinfunction "2_2") (pintype "passive"))
    )
    (net (code "10") (name "Net-(D4-A)") (class "Default")
      (node (ref "C69") (pin "2") (pinfunction "2_2") (pintype "passive"))
      (node (ref "D4") (pin "2") (pinfunction "A_2") (pintype "passive"))
      (node (ref "IC26") (pin "3") (pinfunction "EN_3") (pintype "input"))
      (node (ref "IC8") (pin "7") (pinfunction "PG_7") (pintype "output"))
      (node (ref "R56") (pin "1") (pinfunction "1_1") (pintype "passive"))
    )
    (net (code "11") (name "Net-(D5-A)") (class "Default")
      (node (ref "C66") (pin "2") (pinfunction "2_2") (pintype "passive"))
      (node (ref "D5") (pin "2") (pinfunction "A_2") (pintype "passive"))
      (node (ref "IC15") (pin "6") (pinfunction "IN-_6") (pintype "input"))
      (node (ref "R52") (pin "1") (pinfunction "1_1") (pintype "passive"))
    )
    (net (code "12") (name "Net-(D6-A)") (class "Default")
      (node (ref "D6") (pin "2") (pinfunction "A_2") (pintype "passive"))
      (node (ref "IC13") (pin "5") (pinfunction "~{SHDN}_5") (pintype "input"))
      (node (ref "IC14") (pin "3") (pinfunction "~{SHDN}_3") (pintype "input"))
      (node (ref "IC15") (pin "1") (pinfunction "OUT_1") (pintype "output"))
      (node (ref "IC34") (pin "4") (pinfunction "~{SHDN}_4") (pintype "input"))
      (node (ref "R18") (pin "1") (pinfunction "1_1") (pintype "passive"))
      (node (ref "R52") (pin "2") (pinfunction "2_2") (pintype "passive"))
    )
    (net (code "13") (name "Net-(IC3-RC)") (class "Default")
      (node (ref "IC3") (pin "2") (pinfunction "RC_2") (pintype "input"))
      (node (ref "R8") (pin "2") (pinfunction "2_2") (pintype "passive"))
    )
    (net (code "14") (name "Net-(IC3-TRM)") (class "Default")
      (node (ref "IC3") (pin "6") (pinfunction "TRM_6") (pintype "power_in"))
      (node (ref "R19") (pin "2") (pinfunction "2_2") (pintype "passive"))
      (node (ref "R7") (pin "1") (pinfunction "1_1") (pintype "passive"))
    )
    (net (code "15") (name "Net-(IC4-BYP)") (class "Default")
      (node (ref "C116") (pin "1") (pinfunction "1_1") (pintype "passive"))
      (node (ref "IC4") (pin "3") (pinfunction "BYP_3") (pintype "input"))
    )
    (net (code "16") (name "Net-(IC7-BYP)") (class "Default")
      (node (ref "C47") (pin "1") (pinfunction "1_1") (pintype "passive"))
      (node (ref "IC7") (pin "3") (pinfunction "BYP_3") (pintype "input"))
    )
    (net (code "17") (name "Net-(IC8-FB)") (class "Default")
      (node (ref "IC8") (pin "5") (pinfunction "FB_5") (pintype "input"))
      (node (ref "R24") (pin "1") (pinfunction "1_1") (pintype "passive"))
      (node (ref "R28") (pin "2") (pinfunction "2_2") (pintype "passive"))
    )
    (net (code "18") (name "Net-(IC8-SW)") (class "Default")
      (node (ref "IC8") (pin "9") (pinfunction "SW_9") (pintype "output"))
      (node (ref "L3") (pin "1") (pinfunction "1_1") (pintype "passive"))
    )
    (net (code "19") (name "Net-(IC13-ADJ)") (class "Default")
      (node (ref "IC13") (pin "2") (pinfunction "ADJ_2") (pintype "input"))
      (node (ref "R142") (pin "1") (pinfunction "1_1") (pintype "passive"))
      (node (ref "R143") (pin "2") (pinfunction "2_2") (pintype "passive"))
    )
    (net (code "20") (name "Net-(IC13-BYP)") (class "Default")
      (node (ref "C65") (pin "1") (pinfunction "1_1") (pintype "passive"))
      (node (ref "IC13") (pin "4") (pinfunction "BYP_4") (pintype "passive"))
    )
    (net (code "21") (name "Net-(IC14-ADJ)") (class "Default")
      (node (ref "IC14") (pin "4") (pinfunction "ADJ_4") (pintype "input"))
      (node (ref "IC34") (pin "3") (pinfunction "ADJ_3") (pintype "input"))
      (node (ref "R32") (pin "1") (pinfunction "1_1") (pintype "passive"))
      (node (ref "R38") (pin "2") (pinfunction "2_2") (pintype "passive"))
    )
    (net (code "22") (name "Net-(IC15A-IN-)") (class "Default")
      (node (ref "IC15") (pin "2") (pinfunction "IN-_2") (pintype "input"))
      (node (ref "R23") (pin "1") (pinfunction "1_1") (pintype "passive"))
    )
    (net (code "23") (name "Net-(IC16-ADJ)") (class "Default")
      (node (ref "IC16") (pin "2") (pinfunction "ADJ_2") (pintype "input"))
      (node (ref "R25") (pin "1") (pinfunction "1_1") (pintype "passive"))
      (node (ref "R29") (pin "2") (pinfunction "2_2") (pintype "passive"))
    )
    (net (code "24") (name "Net-(IC16-BYP)") (class "Default")
      (node (ref "C114") (pin "1") (pinfunction "1_1") (pintype "passive"))
      (node (ref "IC16") (pin "4") (pinfunction "BYP_4") (pintype "passive"))
    )
    (net (code "25") (name "Net-(IC26-FB)") (class "Default")
      (node (ref "IC26") (pin "5") (pinfunction "FB_5") (pintype "input"))
      (node (ref "R20") (pin "1") (pinfunction "1_1") (pintype "passive"))
      (node (ref "R21") (pin "2") (pinfunction "2_2") (pintype "passive"))
    )
    (net (code "26") (name "Net-(IC26-SW)") (class "Default")
      (node (ref "IC26") (pin "9") (pinfunction "SW_9") (pintype "output"))
      (node (ref "L5") (pin "1") (pinfunction "1_1") (pintype "passive"))
    )
    (net (code "27") (name "Net-(IC26-VIN)") (class "Default")
      (node (ref "C122") (pin "2") (pinfunction "2_2") (pintype "passive"))
      (node (ref "C123") (pin "2") (pinfunction "2_2") (pintype "passive"))
      (node (ref "C32") (pin "2") (pinfunction "2_2") (pintype "passive"))
      (node (ref "C34") (pin "2") (pinfunction "2_2") (pintype "passive"))
      (node (ref "C36") (pin "2") (pinfunction "2_2") (pintype "passive"))
      (node (ref "C39") (pin "2") (pinfunction "2_2") (pintype "passive"))
      (node (ref "C49") (pin "1") (pinfunction "1_1") (pintype "passive"))
      (node (ref "C63") (pin "2") (pinfunction "2_2") (pintype "passive"))
      (node (ref "C64") (pin "2") (pinfunction "2_2") (pintype "passive"))
      (node (ref "IC26") (pin "2") (pinfunction "VIN_2") (pintype "input"))
      (node (ref "IC3") (pin "1") (pinfunction "+Vin_1") (pintype "power_in"))
      (node (ref "IC8") (pin "2") (pinfunction "VIN_2") (pintype "input"))
      (node (ref "IC8") (pin "3") (pinfunction "EN_3") (pintype "input"))
      (node (ref "L6") (pin "2") (pinfunction "2_2") (pintype "passive"))
    )
    (net (code "28") (name "Net-(IC32-ADJ)") (class "Default")
      (node (ref "IC32") (pin "4") (pinfunction "ADJ_4") (pintype "input"))
      (node (ref "IC4") (pin "4") (pinfunction "ADJ_4") (pintype "input"))
      (node (ref "R26") (pin "1") (pinfunction "1_1") (pintype "passive"))
      (node (ref "R27") (pin "2") (pinfunction "2_2") (pintype "passive"))
    )
    (net (code "29") (name "Net-(IC33-ADJ)") (class "Default")
      (node (ref "IC33") (pin "4") (pinfunction "ADJ_4") (pintype "input"))
      (node (ref "IC7") (pin "4") (pinfunction "ADJ_4") (pintype "input"))
      (node (ref "R53") (pin "1") (pinfunction "1_1") (pintype "passive"))
      (node (ref "R54") (pin "2") (pinfunction "2_2") (pintype "passive"))
    )
    (net (code "30") (name "Net-(IC34-BYP)") (class "Default")
      (node (ref "C83") (pin "1") (pinfunction "1_1") (pintype "passive"))
      (node (ref "IC34") (pin "5") (pinfunction "BYP_5") (pintype "passive"))
    )
    (net (code "31") (name "P2V5A") (class "Default")
      (node (ref "C47") (pin "2") (pinfunction "2_2") (pintype "passive"))
      (node (ref "C55") (pin "2") (pinfunction "2_2") (pintype "passive"))
      (node (ref "C56") (pin "1") (pinfunction "1_1") (pintype "passive"))
      (node (ref "C82") (pin "2") (pinfunction "2_2") (pintype "passive"))
      (node (ref "IC33") (pin "5") (pinfunction "OUT_5") (pintype "power_in"))
      (node (ref "IC7") (pin "5") (pinfunction "OUT_5") (pintype "power_in"))
      (node (ref "R53") (pin "2") (pinfunction "2_2") (pintype "passive"))
      (node (ref "TP10") (pin "1") (pinfunction "1_1") (pintype "bidirectional"))
    )
    (net (code "32") (name "P3V3") (class "Default")
      (node (ref "C120") (pin "2") (pinfunction "2_2") (pintype "passive"))
      (node (ref "C121") (pin "2") (pinfunction "2_2") (pintype "passive"))
      (node (ref "D5") (pin "1") (pinfunction "C_1") (pintype "passive"))
      (node (ref "IC15") (pin "5") (pinfunction "IN+_5") (pintype "input"))
      (node (ref "IC26") (pin "10") (pinfunction "VOS_10") (pintype "input"))
      (node (ref "IC26") (pin "8") (pinfunction "SLEEP_8") (pintype "input"))
      (node (ref "L1") (pin "1") (pinfunction "1_1") (pintype "passive"))
      (node (ref "L5") (pin "2") (pinfunction "2_2") (pintype "passive"))
      (node (ref "R20") (pin "2") (pinfunction "2_2") (pintype "passive"))
      (node (ref "R51") (pin "1") (pinfunction "1_1") (pintype "passive"))
    )
    (net (code "33") (name "P3V3A") (class "Default")
      (node (ref "C50") (pin "1") (pinfunction "1_1") (pintype "passive"))
      (node (ref "C53") (pin "2") (pinfunction "2_2") (pintype "passive"))
      (node (ref "D2") (pin "1") (pinfunction "C_1") (pintype "passive"))
      (node (ref "IC33") (pin "1") (pinfunction "IN_1") (pintype "input"))
      (node (ref "IC33") (pin "3") (pinfunction "~{SHDN}_3") (pintype "input"))
      (node (ref "IC7") (pin "1") (pinfunction "IN_1") (pintype "input"))
      (node (ref "L1") (pin "2") (pinfunction "2_2") (pintype "passive"))
      (node (ref "R23") (pin "2") (pinfunction "2_2") (pintype "passive"))
      (node (ref "TP11") (pin "1") (pinfunction "1_1") (pintype "bidirectional"))
    )
    (net (code "34") (name "P5V0A") (class "Default")
      (node (ref "C114") (pin "2") (pinfunction "2_2") (pintype "passive"))
      (node (ref "C115") (pin "1") (pinfunction "1_1") (pintype "passive"))
      (node (ref "C62") (pin "2") (pinfunction "2_2") (pintype "passive"))
      (node (ref "IC16") (pin "1") (pinfunction "OUT_1") (pintype "power_in"))
      (node (ref "R25") (pin "2") (pinfunction "2_2") (pintype "passive"))
      (node (ref "TP13") (pin "1") (pinfunction "1_1") (pintype "bidirectional"))
    )
    (net (code "35") (name "P6V0") (class "Default")
      (node (ref "C58") (pin "2") (pinfunction "2_2") (pintype "passive"))
      (node (ref "C59") (pin "2") (pinfunction "2_2") (pintype "passive"))
      (node (ref "IC8") (pin "10") (pinfunction "VOS_10") (pintype "input"))
      (node (ref "IC8") (pin "8") (pinfunction "SLEEP_8") (pintype "input"))
      (node (ref "L3") (pin "2") (pinfunction "2_2") (pintype "passive"))
      (node (ref "L4") (pin "1") (pinfunction "1_1") (pintype "passive"))
      (node (ref "R24") (pin "2") (pinfunction "2_2") (pintype "passive"))
      (node (ref "R57") (pin "2") (pinfunction "2_2") (pintype "passive"))
    )
    (net (code "36") (name "P6V0A") (class "Default")
      (node (ref "C60") (pin "1") (pinfunction "1_1") (pintype "passive"))
      (node (ref "C61") (pin "2") (pinfunction "2_2") (pintype "passive"))
      (node (ref "D4") (pin "1") (pinfunction "C_1") (pintype "passive"))
      (node (ref "IC16") (pin "5") (pinfunction "~{SHDN}_5") (pintype "input"))
      (node (ref "IC16") (pin "8") (pinfunction "IN_8") (pintype "input"))
      (node (ref "L4") (pin "2") (pinfunction "2_2") (pintype "passive"))
      (node (ref "R18") (pin "2") (pinfunction "2_2") (pintype "passive"))
      (node (ref "R56") (pin "2") (pinfunction "2_2") (pintype "passive"))
      (node (ref "TP12") (pin "1") (pinfunction "1_1") (pintype "bidirectional"))
    )
    (net (code "37") (name "P12V0") (class "Default")
      (node (ref "C48") (pin "2") (pinfunction "2_2") (pintype "passive"))
      (node (ref "IC15") (pin "8") (pinfunction "V+_8") (pintype "power_in"))
      (node (ref "L6") (pin "1") (pinfunction "1_1") (pintype "passive"))
    )
    (net (code "38") (name "P12V0A") (class "Default")
      (node (ref "C30") (pin "2") (pinfunction "2_2") (pintype "passive"))
      (node (ref "C51") (pin "1") (pinfunction "1_1") (pintype "passive"))
      (node (ref "C65") (pin "2") (pinfunction "2_2") (pintype "passive"))
      (node (ref "D8") (pin "1") (pinfunction "C_1") (pintype "passive"))
      (node (ref "IC13") (pin "1") (pinfunction "OUT_1") (pintype "power_in"))
      (node (ref "R142") (pin "2") (pinfunction "2_2") (pintype "passive"))
      (node (ref "TP7") (pin "1") (pinfunction "1_1") (pintype "bidirectional"))
    )
    (net (code "39") (name "P13V0") (class "Default")
      (node (ref "C112") (pin "2") (pinfunction "2_2") (pintype "passive"))
      (node (ref "C117") (pin "2") (pinfunction "2_2") (pintype "passive"))
      (node (ref "C29") (pin "2") (pinfunction "2_2") (pintype "passive"))
      (node (ref "C77") (pin "1") (pinfunction "1_1") (pintype "passive"))
      (node (ref "IC13") (pin "8") (pinfunction "IN_8") (pintype "input"))
      (node (ref "IC32") (pin "1") (pinfunction "IN_1") (pintype "input"))
      (node (ref "IC32") (pin "3") (pinfunction "~{SHDN}_3") (pintype "input"))
      (node (ref "IC4") (pin "1") (pinfunction "IN_1") (pintype "input"))
      (node (ref "L11") (pin "2") (pinfunction "2_2") (pintype "passive"))
    )
    (net (code "40") (name "P13V0S") (class "Default")
      (node (ref "C26") (pin "2") (pinfunction "2_2") (pintype "passive"))
      (node (ref "IC3") (pin "7") (pinfunction "+Vout_7") (pintype "power_in"))
      (node (ref "L10") (pin "1") (pinfunction "1_1") (pintype "passive"))
      (node (ref "R7") (pin "2") (pinfunction "2_2") (pintype "passive"))
    )
    (net (code "41") (name "REF_P4V096") (class "Default")
      (node (ref "R22") (pin "1") (pinfunction "1_1") (pintype "passive"))
    )
    (net (code "42") (name "REF_VCC") (class "Default")
      (node (ref "C116") (pin "2") (pinfunction "2_2") (pintype "passive"))
      (node (ref "C118") (pin "1") (pinfunction "1_1") (pintype "passive"))
      (node (ref "C45") (pin "2") (pinfunction "2_2") (pintype "passive"))
      (node (ref "C81") (pin "2") (pinfunction "2_2") (pintype "passive"))
      (node (ref "IC32") (pin "5") (pinfunction "OUT_5") (pintype "power_in"))
      (node (ref "IC4") (pin "5") (pinfunction "OUT_5") (pintype "power_in"))
      (node (ref "R26") (pin "2") (pinfunction "2_2") (pintype "passive"))
      (node (ref "TP8") (pin "1") (pinfunction "1_1") (pintype "bidirectional"))
    )
    (net (code "43") (name "unconnected-(IC8-NC-Pad4)") (class "Default")
      (node (ref "IC8") (pin "4") (pinfunction "NC_4") (pintype "passive"))
    )
    (net (code "44") (name "unconnected-(IC26-NC-Pad4)") (class "Default")
      (node (ref "IC26") (pin "4") (pinfunction "NC_4") (pintype "passive"))
    )
  )
)
